# SparkFun_BMP180_Breakout.net
KiCad netlist of a schematic drawn in EAGLE
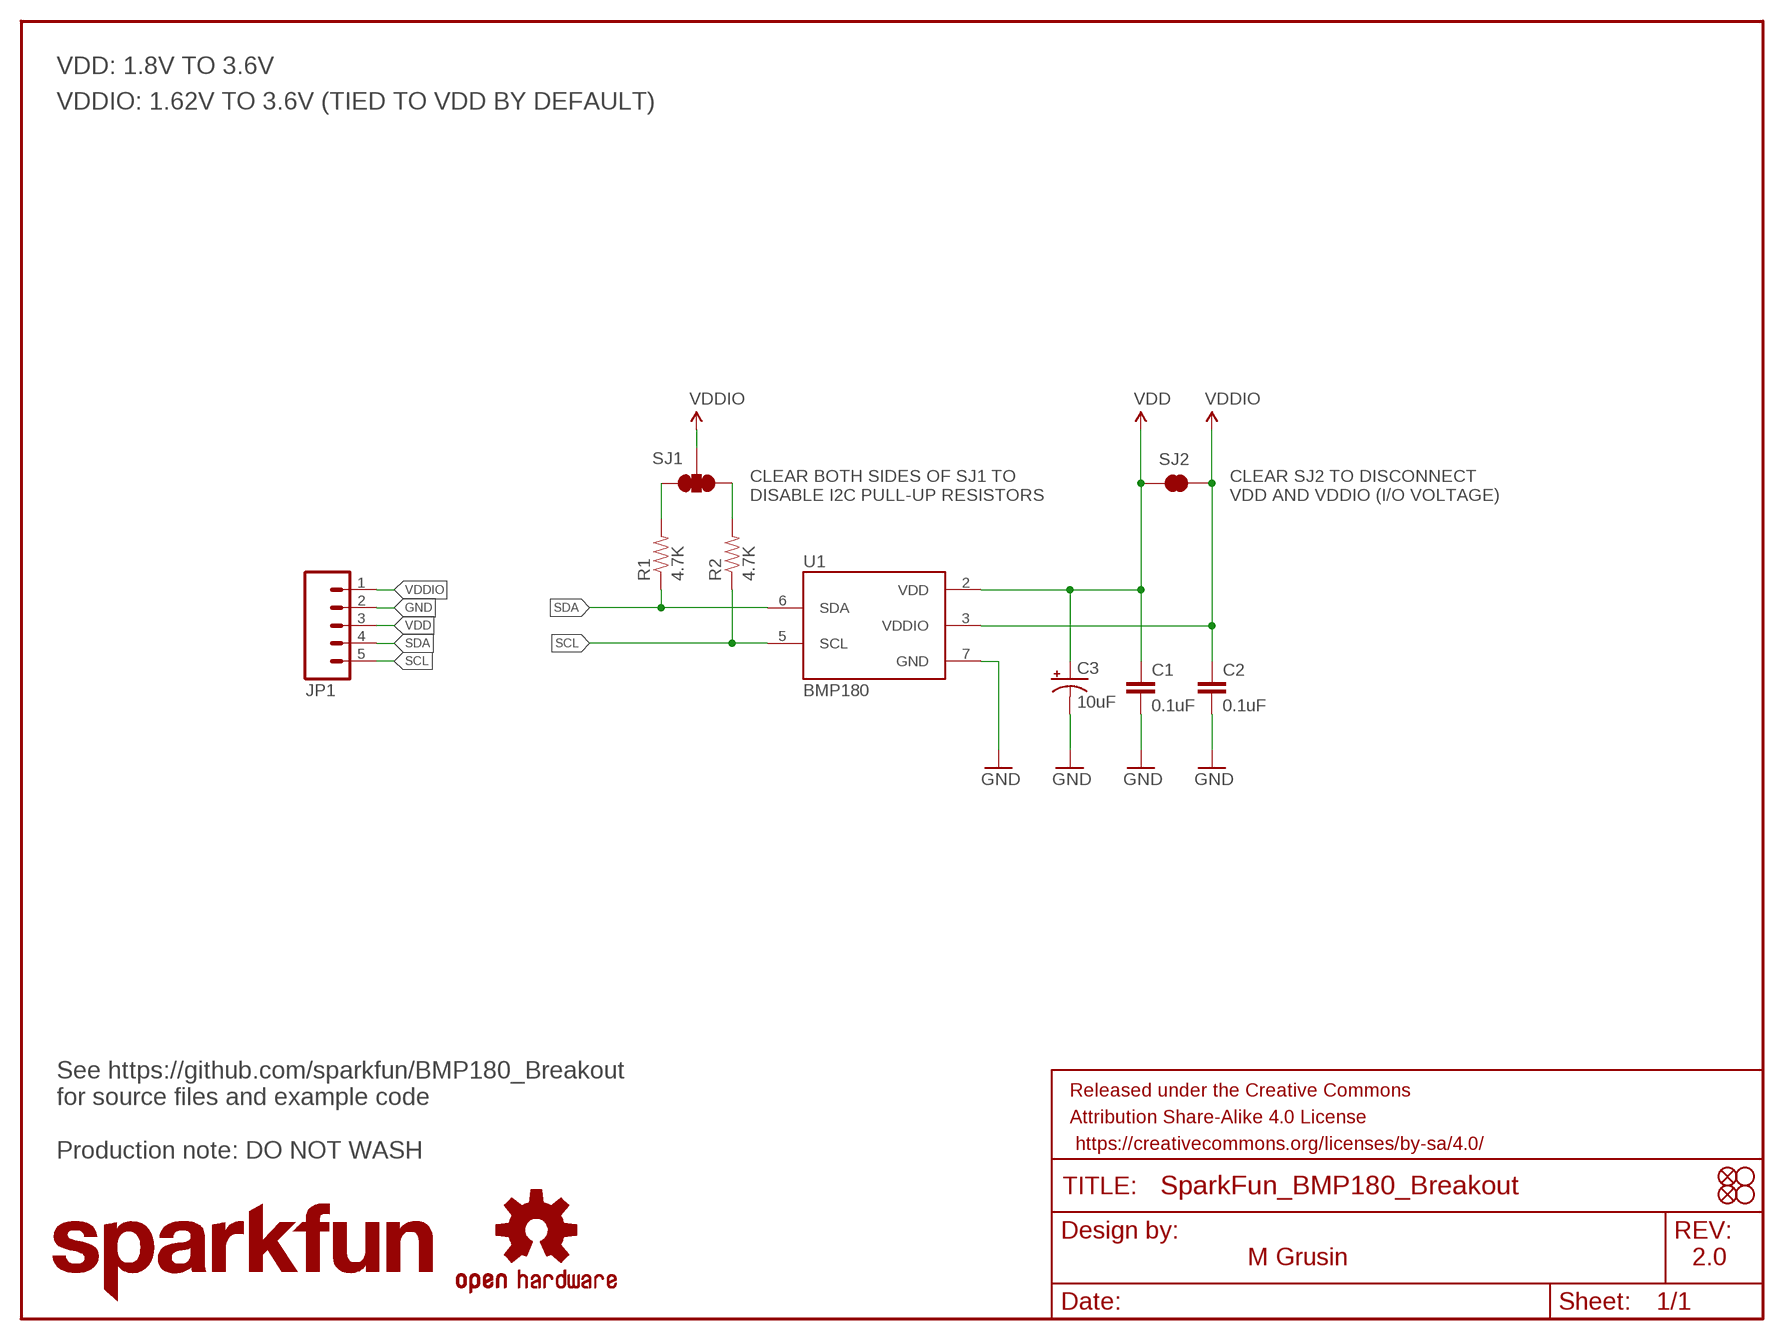
[diagram p0: schematic, sheet 1]

(export (version "E")
  (design (tool "Eeschema 10.0.6"))
  (components
    (comp (ref "C1")
      (value "0.1uF")
      (footprint "eagle-import:0603-CAP")
      (libsource (lib "eagle-import") (part "CAP0603-CAP"))
    )
    (comp (ref "C2")
      (value "0.1uF")
      (footprint "eagle-import:0603-CAP")
      (libsource (lib "eagle-import") (part "CAP0603-CAP"))
    )
    (comp (ref "C3")
      (value "10uF")
      (footprint "eagle-import:EIA3216")
      (libsource (lib "eagle-import") (part "10UF-16V-10%(TANT)"))
    )
    (comp (ref "FID1")
      (value "FIDUCIALUFIDUCIAL")
      (footprint "eagle-import:MICRO-FIDUCIAL")
      (libsource (lib "eagle-import") (part "FIDUCIALUFIDUCIAL"))
    )
    (comp (ref "FID2")
      (value "FIDUCIALUFIDUCIAL")
      (footprint "eagle-import:MICRO-FIDUCIAL")
      (libsource (lib "eagle-import") (part "FIDUCIALUFIDUCIAL"))
    )
    (comp (ref "FRAME1")
      (value "FRAME-LETTER")
      (footprint "eagle-import:CREATIVE_COMMONS")
      (libsource (lib "eagle-import") (part "FRAME-LETTER"))
    )
    (comp (ref "JP1")
      (value "M05_ROUNDONLY_NOSILK")
      (footprint "eagle-import:1X05_ROUNDONLY_NOSILK")
      (libsource (lib "eagle-import") (part "M05_ROUNDONLY_NOSILK"))
    )
    (comp (ref "LOGO2")
      (value "OSHW-LOGOS")
      (footprint "eagle-import:OSHW-LOGO-S")
      (libsource (lib "eagle-import") (part "OSHW-LOGOS"))
    )
    (comp (ref "LOGO3")
      (value "SFE_LOGO_NAME.1_INCH")
      (footprint "eagle-import:SFE_LOGO_NAME_.1")
      (libsource (lib "eagle-import") (part "SFE_LOGO_NAME.1_INCH"))
    )
    (comp (ref "R1")
      (value "4.7K")
      (footprint "eagle-import:0603-RES")
      (libsource (lib "eagle-import") (part "RESISTOR0603-RES"))
    )
    (comp (ref "R2")
      (value "4.7K")
      (footprint "eagle-import:0603-RES")
      (libsource (lib "eagle-import") (part "RESISTOR0603-RES"))
    )
    (comp (ref "SJ1")
      (value "SOLDERJUMPER_2WAYPASTE1&2&3")
      (footprint "eagle-import:SJ_3_PASTE1&2&3")
      (libsource (lib "eagle-import") (part "SOLDERJUMPER_2WAYPASTE1&2&3"))
    )
    (comp (ref "SJ2")
      (value "SOLDERJUMPERNC")
      (footprint "eagle-import:SJ_2S")
      (libsource (lib "eagle-import") (part "SOLDERJUMPERNC"))
    )
    (comp (ref "STANDOFF1")
      (value "STAND-OFF")
      (footprint "eagle-import:STAND-OFF")
      (libsource (lib "eagle-import") (part "STAND-OFF"))
    )
    (comp (ref "STANDOFF2")
      (value "STAND-OFF")
      (footprint "eagle-import:STAND-OFF")
      (libsource (lib "eagle-import") (part "STAND-OFF"))
    )
    (comp (ref "U1")
      (value "BMP180")
      (footprint "eagle-import:BMP180")
      (libsource (lib "eagle-import") (part "BMP180"))
    )
  )
  (nets
    (net (code "1") (name "GND") (class "Default")
      (node (ref "C1") (pin "2") (pinfunction "2_2") (pintype "passive"))
      (node (ref "C2") (pin "2") (pinfunction "2_2") (pintype "passive"))
      (node (ref "C3") (pin "C") (pinfunction "-_C") (pintype "passive"))
      (node (ref "JP1") (pin "2") (pinfunction "2_2") (pintype "passive"))
      (node (ref "U1") (pin "7") (pinfunction "GND_7") (pintype "power_in"))
    )
    (net (code "2") (name "Net-(R1-Pad2)") (class "Default")
      (node (ref "R1") (pin "2") (pinfunction "2_2") (pintype "passive"))
      (node (ref "SJ1") (pin "3") (pinfunction "3_3") (pintype "passive"))
    )
    (net (code "3") (name "Net-(R2-Pad2)") (class "Default")
      (node (ref "R2") (pin "2") (pinfunction "2_2") (pintype "passive"))
      (node (ref "SJ1") (pin "1") (pinfunction "1_1") (pintype "passive"))
    )
    (net (code "4") (name "SCL") (class "Default")
      (node (ref "JP1") (pin "5") (pinfunction "5_5") (pintype "passive"))
      (node (ref "R2") (pin "1") (pinfunction "1_1") (pintype "passive"))
      (node (ref "U1") (pin "5") (pinfunction "SCL_5") (pintype "input"))
    )
    (net (code "5") (name "SDA") (class "Default")
      (node (ref "JP1") (pin "4") (pinfunction "4_4") (pintype "passive"))
      (node (ref "R1") (pin "1") (pinfunction "1_1") (pintype "passive"))
      (node (ref "U1") (pin "6") (pinfunction "SDA_6") (pintype "bidirectional"))
    )
    (net (code "6") (name "VDD") (class "Default")
      (node (ref "C1") (pin "1") (pinfunction "1_1") (pintype "passive"))
      (node (ref "C3") (pin "A") (pinfunction "+_A") (pintype "passive"))
      (node (ref "JP1") (pin "3") (pinfunction "3_3") (pintype "passive"))
      (node (ref "SJ2") (pin "1") (pinfunction "1_1") (pintype "passive"))
      (node (ref "U1") (pin "2") (pinfunction "VDD_2") (pintype "power_in"))
    )
    (net (code "7") (name "VDDIO") (class "Default")
      (node (ref "C2") (pin "1") (pinfunction "1_1") (pintype "passive"))
      (node (ref "JP1") (pin "1") (pinfunction "1_1") (pintype "passive"))
      (node (ref "SJ1") (pin "2") (pinfunction "2_2") (pintype "passive"))
      (node (ref "SJ2") (pin "2") (pinfunction "2_2") (pintype "passive"))
      (node (ref "U1") (pin "3") (pinfunction "VDDIO_3") (pintype "power_in"))
    )
  )
)
